# RAM-k4s561632h-uc75.net
KiCad netlist of a schematic drawn in Altium Designer
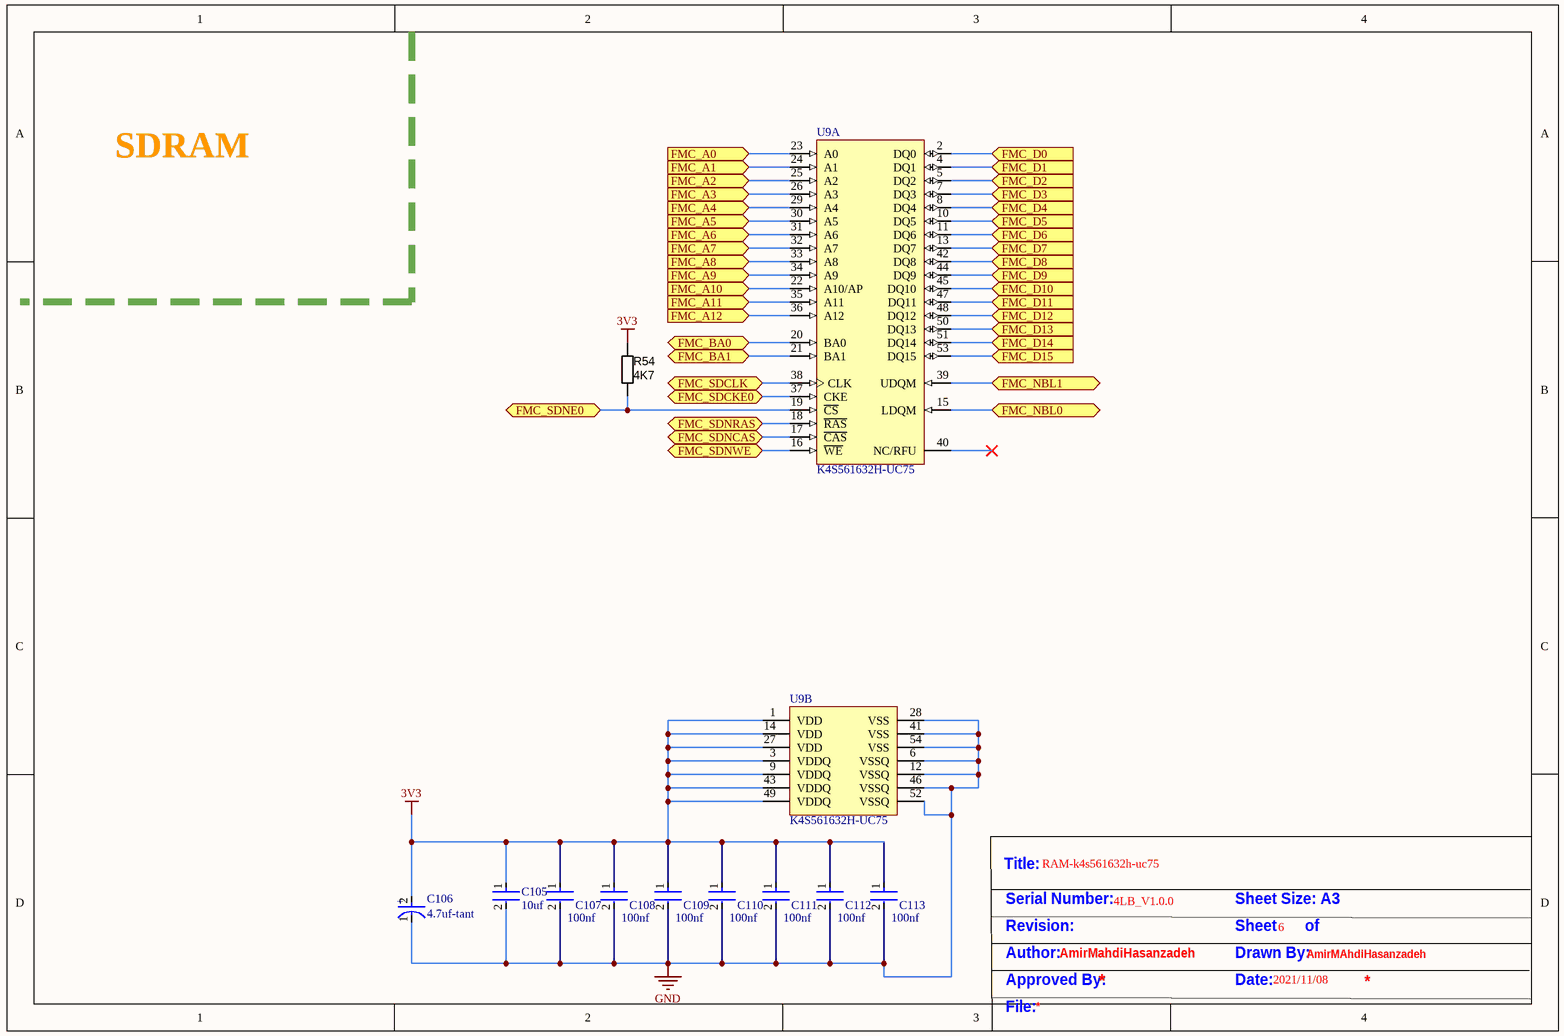
[diagram p0: RAM-k4s561632h-uc75.SchDoc]

(export (version "E")
  (design (tool "Eeschema 10.0.6"))
  (components
    (comp (ref "C105")
      (value "10uf")
      (footprint "FP-C3216-160-0_2-IPC_A")
      (description "Multilayer Ceramic Capacitors 10uF ±10% 50V X5R SMD 1206")
      (fields (field (name "TOLERANCE") "10%") (field (name "VOLTAGE") "50V"))
      (libsource (lib "Altium Content Vault") (part "11868f565c42a9108669ba33697ecf6"))
    )
    (comp (ref "C106")
      (value "4.7uf-tant")
      (footprint "FP-T491A475K016AT-MFG")
      (description "CAP TANT 4.7UF 10% 16V 1206")
      (fields (field (name "TOLERANCE") "10%") (field (name "VOLTAGE") "16V"))
      (libsource (lib "Altium Content Vault") (part "cf48714ba7e38822c1575c7ec0b6d1f"))
    )
    (comp (ref "C107")
      (value "100nf")
      (footprint "FP-CGA3E-0_3-0_1-IPC_A")
      (description "Cap Ceramic 100nF 50V X7R 10% Pad SMD 0603 +125°C Automotive T/R")
      (fields (field (name "TOLERANCE") "10%") (field (name "VOLTAGE") "50V"))
      (libsource (lib "Altium Content Vault") (part "b4654b650e69147ec39a6b967a45e02"))
    )
    (comp (ref "C108")
      (value "100nf")
      (footprint "FP-CGA3E-0_3-0_1-IPC_A")
      (description "Cap Ceramic 100nF 50V X7R 10% Pad SMD 0603 +125°C Automotive T/R")
      (fields (field (name "TOLERANCE") "10%") (field (name "VOLTAGE") "50V"))
      (libsource (lib "Altium Content Vault") (part "b4654b650e69147ec39a6b967a45e02"))
    )
    (comp (ref "C109")
      (value "100nf")
      (footprint "FP-CGA3E-0_3-0_1-IPC_A")
      (description "Cap Ceramic 100nF 50V X7R 10% Pad SMD 0603 +125°C Automotive T/R")
      (fields (field (name "TOLERANCE") "10%") (field (name "VOLTAGE") "50V"))
      (libsource (lib "Altium Content Vault") (part "b4654b650e69147ec39a6b967a45e02"))
    )
    (comp (ref "C110")
      (value "100nf")
      (footprint "FP-CGA3E-0_3-0_1-IPC_A")
      (description "Cap Ceramic 100nF 50V X7R 10% Pad SMD 0603 +125°C Automotive T/R")
      (fields (field (name "TOLERANCE") "10%") (field (name "VOLTAGE") "50V"))
      (libsource (lib "Altium Content Vault") (part "b4654b650e69147ec39a6b967a45e02"))
    )
    (comp (ref "C111")
      (value "100nf")
      (footprint "FP-CGA3E-0_3-0_1-IPC_A")
      (description "Cap Ceramic 100nF 50V X7R 10% Pad SMD 0603 +125°C Automotive T/R")
      (fields (field (name "TOLERANCE") "10%") (field (name "VOLTAGE") "50V"))
      (libsource (lib "Altium Content Vault") (part "b4654b650e69147ec39a6b967a45e02"))
    )
    (comp (ref "C112")
      (value "100nf")
      (footprint "FP-CGA3E-0_3-0_1-IPC_A")
      (description "Cap Ceramic 100nF 50V X7R 10% Pad SMD 0603 +125°C Automotive T/R")
      (fields (field (name "TOLERANCE") "10%") (field (name "VOLTAGE") "50V"))
      (libsource (lib "Altium Content Vault") (part "b4654b650e69147ec39a6b967a45e02"))
    )
    (comp (ref "C113")
      (value "100nf")
      (footprint "FP-CGA3E-0_3-0_1-IPC_A")
      (description "Cap Ceramic 100nF 50V X7R 10% Pad SMD 0603 +125°C Automotive T/R")
      (fields (field (name "TOLERANCE") "10%") (field (name "VOLTAGE") "50V"))
      (libsource (lib "Altium Content Vault") (part "b4654b650e69147ec39a6b967a45e02"))
    )
    (comp (ref "R54")
      (value "4K7")
      (footprint "RESC1608X55N")
      (description "Resistor SMD chip 4.7k Ohm 0.1W 5% 0603")
      (fields (field (name "TOLERANCE") "±5%") (field (name "Comment") "Thick Film"))
      (libsource (lib "PBL - Resistors") (part "RES_4K7_0603_5%"))
    )
    (comp (ref "U9")
      (value "K4S561632H-UC75")
      (footprint "SAMS-TSOP-54_L")
      (description "H-Die SDRAM Specification, 256 Mbits, 130 mA, 3.3 V, 0 to 70 degC, 54-Pin TSOP, RoHS")
      (fields (field (name "MANUFACTURER") "Samsung Electro-Mechanics"))
      (libsource (lib "Altium Content Vault") (part "SAMS-K4S561632H-TSOP-54"))
    )
  )
  (nets
    (net (code "1") (name "/FMC_A0") (class "Default")
      (node (ref "U9") (pin "23") (pinfunction "A0_23") (pintype "input"))
    )
    (net (code "2") (name "/FMC_A1") (class "Default")
      (node (ref "U9") (pin "24") (pinfunction "A1_24") (pintype "input"))
    )
    (net (code "3") (name "/FMC_A2") (class "Default")
      (node (ref "U9") (pin "25") (pinfunction "A2_25") (pintype "input"))
    )
    (net (code "4") (name "/FMC_A3") (class "Default")
      (node (ref "U9") (pin "26") (pinfunction "A3_26") (pintype "input"))
    )
    (net (code "5") (name "/FMC_A4") (class "Default")
      (node (ref "U9") (pin "29") (pinfunction "A4_29") (pintype "input"))
    )
    (net (code "6") (name "/FMC_A5") (class "Default")
      (node (ref "U9") (pin "30") (pinfunction "A5_30") (pintype "input"))
    )
    (net (code "7") (name "/FMC_A6") (class "Default")
      (node (ref "U9") (pin "31") (pinfunction "A6_31") (pintype "input"))
    )
    (net (code "8") (name "/FMC_A7") (class "Default")
      (node (ref "U9") (pin "32") (pinfunction "A7_32") (pintype "input"))
    )
    (net (code "9") (name "/FMC_A8") (class "Default")
      (node (ref "U9") (pin "33") (pinfunction "A8_33") (pintype "input"))
    )
    (net (code "10") (name "/FMC_A9") (class "Default")
      (node (ref "U9") (pin "34") (pinfunction "A9_34") (pintype "input"))
    )
    (net (code "11") (name "/FMC_A10") (class "Default")
      (node (ref "U9") (pin "22") (pinfunction "A10/AP_22") (pintype "input"))
    )
    (net (code "12") (name "/FMC_A11") (class "Default")
      (node (ref "U9") (pin "35") (pinfunction "A11_35") (pintype "input"))
    )
    (net (code "13") (name "/FMC_A12") (class "Default")
      (node (ref "U9") (pin "36") (pinfunction "A12_36") (pintype "input"))
    )
    (net (code "14") (name "/FMC_BA0") (class "Default")
      (node (ref "U9") (pin "20") (pinfunction "BA0_20") (pintype "input"))
    )
    (net (code "15") (name "/FMC_BA1") (class "Default")
      (node (ref "U9") (pin "21") (pinfunction "BA1_21") (pintype "input"))
    )
    (net (code "16") (name "/FMC_D0") (class "Default")
      (node (ref "U9") (pin "2") (pinfunction "DQ0_2") (pintype "bidirectional"))
    )
    (net (code "17") (name "/FMC_D1") (class "Default")
      (node (ref "U9") (pin "4") (pinfunction "DQ1_4") (pintype "bidirectional"))
    )
    (net (code "18") (name "/FMC_D2") (class "Default")
      (node (ref "U9") (pin "5") (pinfunction "DQ2_5") (pintype "bidirectional"))
    )
    (net (code "19") (name "/FMC_D3") (class "Default")
      (node (ref "U9") (pin "7") (pinfunction "DQ3_7") (pintype "bidirectional"))
    )
    (net (code "20") (name "/FMC_D4") (class "Default")
      (node (ref "U9") (pin "8") (pinfunction "DQ4_8") (pintype "bidirectional"))
    )
    (net (code "21") (name "/FMC_D5") (class "Default")
      (node (ref "U9") (pin "10") (pinfunction "DQ5_10") (pintype "bidirectional"))
    )
    (net (code "22") (name "/FMC_D6") (class "Default")
      (node (ref "U9") (pin "11") (pinfunction "DQ6_11") (pintype "bidirectional"))
    )
    (net (code "23") (name "/FMC_D7") (class "Default")
      (node (ref "U9") (pin "13") (pinfunction "DQ7_13") (pintype "bidirectional"))
    )
    (net (code "24") (name "/FMC_D8") (class "Default")
      (node (ref "U9") (pin "42") (pinfunction "DQ8_42") (pintype "bidirectional"))
    )
    (net (code "25") (name "/FMC_D9") (class "Default")
      (node (ref "U9") (pin "44") (pinfunction "DQ9_44") (pintype "bidirectional"))
    )
    (net (code "26") (name "/FMC_D10") (class "Default")
      (node (ref "U9") (pin "45") (pinfunction "DQ10_45") (pintype "bidirectional"))
    )
    (net (code "27") (name "/FMC_D11") (class "Default")
      (node (ref "U9") (pin "47") (pinfunction "DQ11_47") (pintype "bidirectional"))
    )
    (net (code "28") (name "/FMC_D12") (class "Default")
      (node (ref "U9") (pin "48") (pinfunction "DQ12_48") (pintype "bidirectional"))
    )
    (net (code "29") (name "/FMC_D13") (class "Default")
      (node (ref "U9") (pin "50") (pinfunction "DQ13_50") (pintype "bidirectional"))
    )
    (net (code "30") (name "/FMC_D14") (class "Default")
      (node (ref "U9") (pin "51") (pinfunction "DQ14_51") (pintype "bidirectional"))
    )
    (net (code "31") (name "/FMC_D15") (class "Default")
      (node (ref "U9") (pin "53") (pinfunction "DQ15_53") (pintype "bidirectional"))
    )
    (net (code "32") (name "/FMC_NBL0") (class "Default")
      (node (ref "U9") (pin "15") (pinfunction "LDQM_15") (pintype "input"))
    )
    (net (code "33") (name "/FMC_NBL1") (class "Default")
      (node (ref "U9") (pin "39") (pinfunction "UDQM_39") (pintype "input"))
    )
    (net (code "34") (name "/FMC_SDCKE0") (class "Default")
      (node (ref "U9") (pin "37") (pinfunction "CKE_37") (pintype "input"))
    )
    (net (code "35") (name "/FMC_SDCLK") (class "Default")
      (node (ref "U9") (pin "38") (pinfunction "CLK_38") (pintype "input"))
    )
    (net (code "36") (name "/FMC_SDNCAS") (class "Default")
      (node (ref "U9") (pin "17") (pinfunction "~{CAS}_17") (pintype "input"))
    )
    (net (code "37") (name "/FMC_SDNE0") (class "Default")
      (node (ref "R54") (pin "2") (pinfunction "2_2") (pintype "passive"))
      (node (ref "U9") (pin "19") (pinfunction "~{CS}_19") (pintype "input"))
    )
    (net (code "38") (name "/FMC_SDNRAS") (class "Default")
      (node (ref "U9") (pin "18") (pinfunction "~{RAS}_18") (pintype "input"))
    )
    (net (code "39") (name "/FMC_SDNWE") (class "Default")
      (node (ref "U9") (pin "16") (pinfunction "~{WE}_16") (pintype "input"))
    )
    (net (code "40") (name "3V3") (class "Default")
      (node (ref "C105") (pin "1") (pinfunction "1_1") (pintype "passive"))
      (node (ref "C106") (pin "2") (pinfunction "A_2") (pintype "passive"))
      (node (ref "C107") (pin "1") (pinfunction "1_1") (pintype "passive"))
      (node (ref "C108") (pin "1") (pinfunction "1_1") (pintype "passive"))
      (node (ref "C109") (pin "1") (pinfunction "1_1") (pintype "passive"))
      (node (ref "C110") (pin "1") (pinfunction "1_1") (pintype "passive"))
      (node (ref "C111") (pin "1") (pinfunction "1_1") (pintype "passive"))
      (node (ref "C112") (pin "1") (pinfunction "1_1") (pintype "passive"))
      (node (ref "C113") (pin "1") (pinfunction "1_1") (pintype "passive"))
      (node (ref "R54") (pin "1") (pinfunction "1_1") (pintype "passive"))
      (node (ref "U9") (pin "1") (pinfunction "VDD_1") (pintype "power_in"))
      (node (ref "U9") (pin "14") (pinfunction "VDD_14") (pintype "power_in"))
      (node (ref "U9") (pin "27") (pinfunction "VDD_27") (pintype "power_in"))
      (node (ref "U9") (pin "3") (pinfunction "VDDQ_3") (pintype "power_in"))
      (node (ref "U9") (pin "43") (pinfunction "VDDQ_43") (pintype "power_in"))
      (node (ref "U9") (pin "49") (pinfunction "VDDQ_49") (pintype "power_in"))
      (node (ref "U9") (pin "9") (pinfunction "VDDQ_9") (pintype "power_in"))
    )
    (net (code "41") (name "GND") (class "Default")
      (node (ref "C105") (pin "2") (pinfunction "2_2") (pintype "passive"))
      (node (ref "C106") (pin "1") (pinfunction "C_1") (pintype "passive"))
      (node (ref "C107") (pin "2") (pinfunction "2_2") (pintype "passive"))
      (node (ref "C108") (pin "2") (pinfunction "2_2") (pintype "passive"))
      (node (ref "C109") (pin "2") (pinfunction "2_2") (pintype "passive"))
      (node (ref "C110") (pin "2") (pinfunction "2_2") (pintype "passive"))
      (node (ref "C111") (pin "2") (pinfunction "2_2") (pintype "passive"))
      (node (ref "C112") (pin "2") (pinfunction "2_2") (pintype "passive"))
      (node (ref "C113") (pin "2") (pinfunction "2_2") (pintype "passive"))
      (node (ref "U9") (pin "12") (pinfunction "VSSQ_12") (pintype "power_in"))
      (node (ref "U9") (pin "28") (pinfunction "VSS_28") (pintype "power_in"))
      (node (ref "U9") (pin "41") (pinfunction "VSS_41") (pintype "power_in"))
      (node (ref "U9") (pin "46") (pinfunction "VSSQ_46") (pintype "power_in"))
      (node (ref "U9") (pin "52") (pinfunction "VSSQ_52") (pintype "power_in"))
      (node (ref "U9") (pin "54") (pinfunction "VSS_54") (pintype "power_in"))
      (node (ref "U9") (pin "6") (pinfunction "VSSQ_6") (pintype "power_in"))
    )
    (net (code "42") (name "unconnected-(U9A-NC{slash}RFU-Pad40)") (class "Default")
      (node (ref "U9") (pin "40") (pinfunction "NC/RFU_40") (pintype "passive+no_connect"))
    )
  )
)
